# pm25.net
KiCad netlist of a schematic drawn in EAGLE
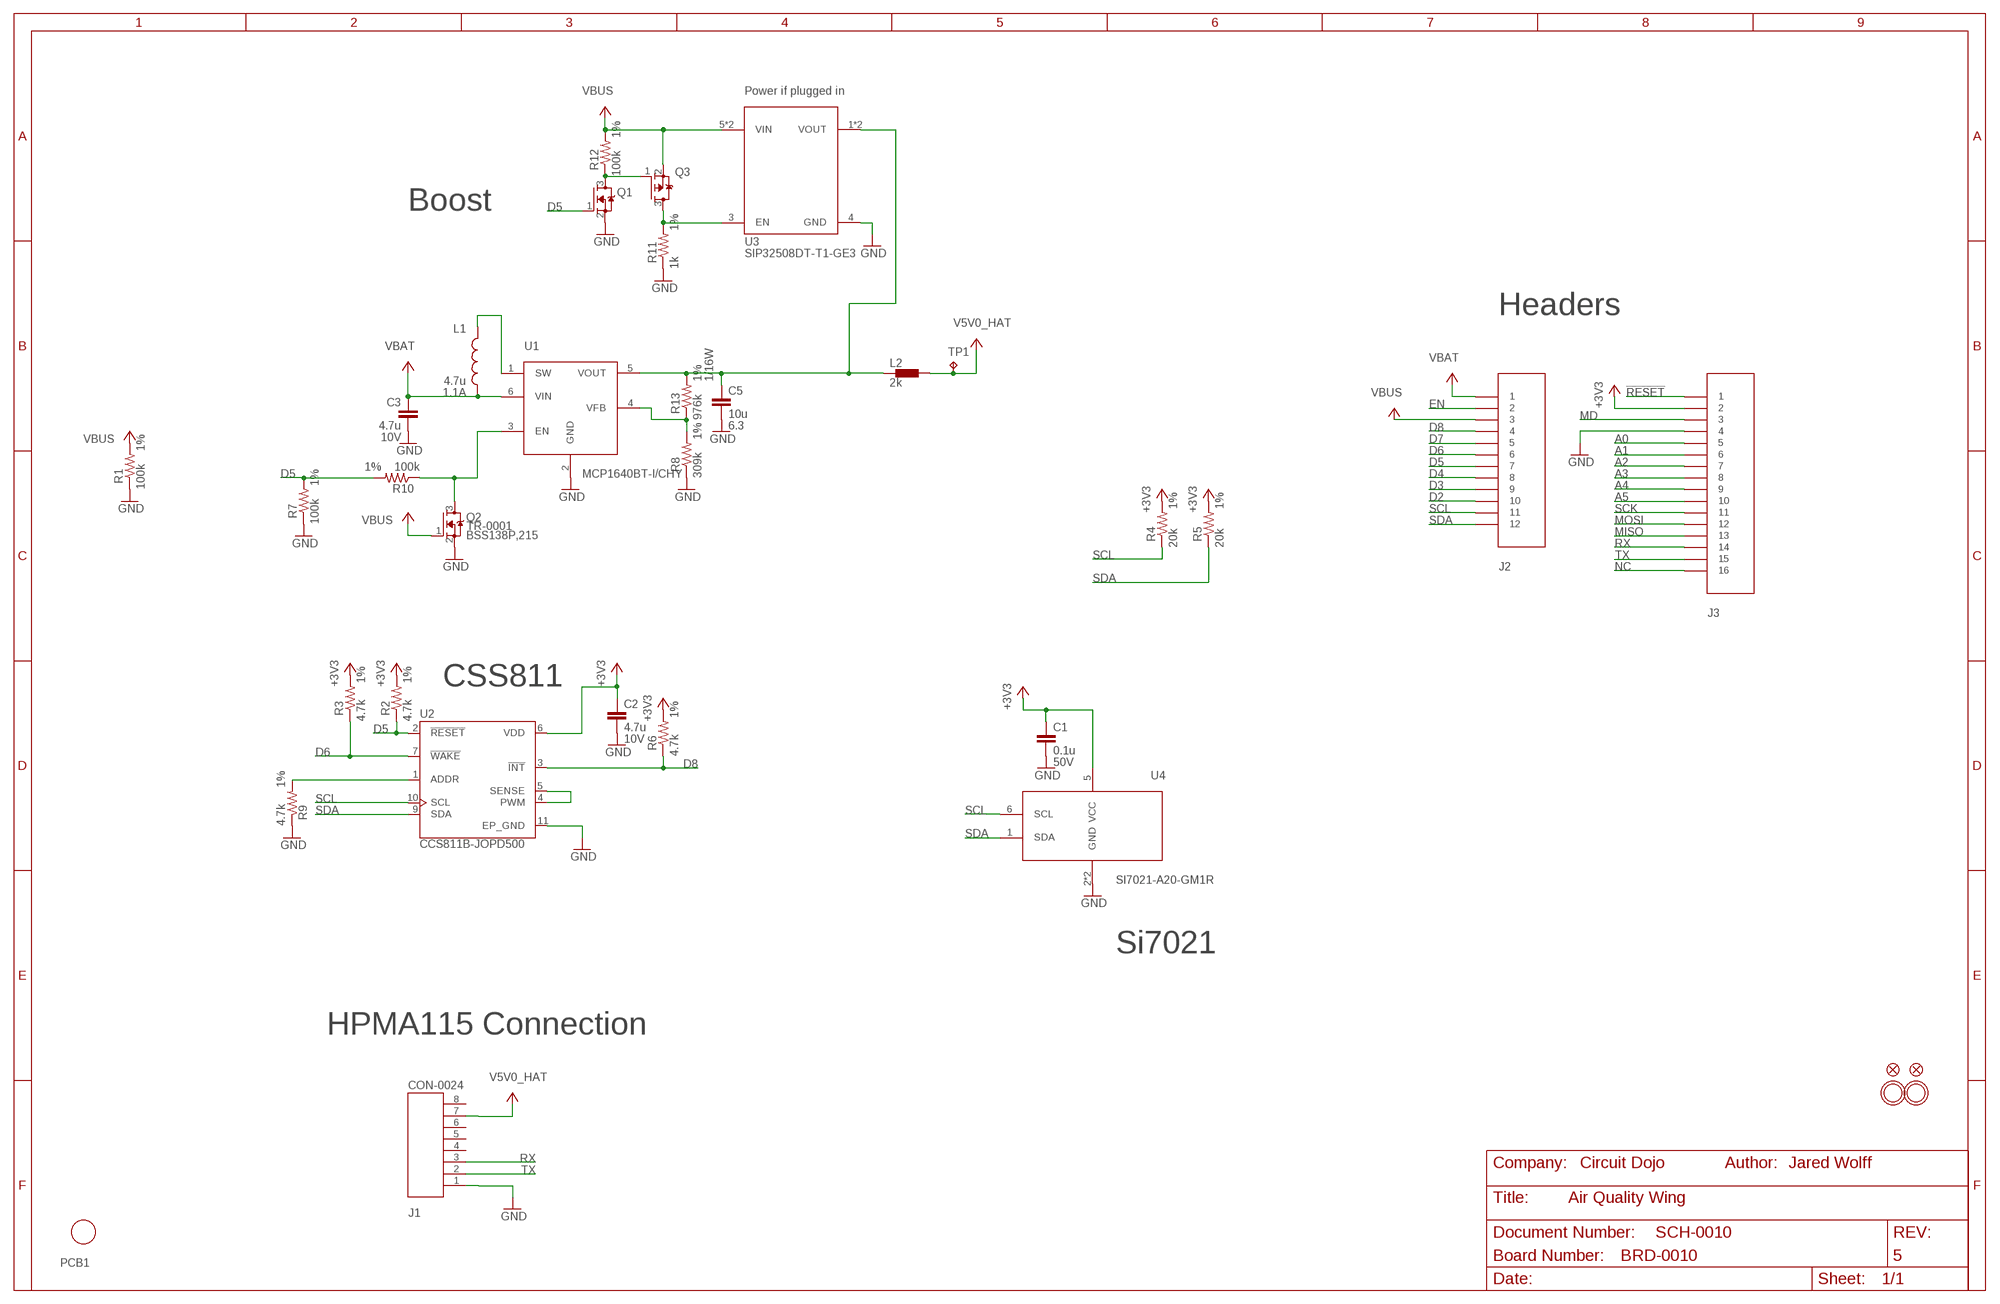
[diagram p0: schematic, sheet 1]

(export (version "E")
  (design (tool "Eeschema 10.0.6"))
  (components
    (comp (ref "C1")
      (value "0.1u")
      (footprint "eagle-import:CAPC1005X55N")
      (fields
        (field (name "VOLTHIGH") "50V")
        (field (name "MF") "Taiyo Yuden")
        (field (name "MPN") "UMK105BJ104KV-F")
      )
      (libsource (lib "eagle-import") (part "CAP-0017"))
    )
    (comp (ref "C2")
      (value "4.7u")
      (footprint "eagle-import:C0603")
      (fields (field (name "VOLTHIGH") "10V") (field (name "MPN") "CL10A475MP5LNNC"))
      (libsource (lib "eagle-import") (part "CAP-0010"))
    )
    (comp (ref "C3")
      (value "4.7u")
      (footprint "eagle-import:C0603")
      (fields (field (name "VOLTHIGH") "10V") (field (name "MPN") "CL10A475MP5LNNC"))
      (libsource (lib "eagle-import") (part "CAP-0010"))
    )
    (comp (ref "C5")
      (value "10u")
      (footprint "eagle-import:C0603")
      (fields (field (name "MPN") "JMK107ABJ106MA-T") (field (name "VOLTHIGH") "6.3"))
      (libsource (lib "eagle-import") (part "CAP-0603-10U-6.3V"))
    )
    (comp (ref "J1")
      (value "CON-0024")
      (footprint "eagle-import:0532610871")
      (fields (field (name "MPN") "0532610871"))
      (libsource (lib "eagle-import") (part "CON-0024"))
    )
    (comp (ref "J2")
      (value "HEADER-12")
      (footprint "eagle-import:CON-HEADER-1X12")
      (fields (field (name "MF") "Sullins Connector Solutions") (field (name "MPN") "PPPC121LFBN-RC"))
      (libsource (lib "eagle-import") (part "HEADER-12"))
    )
    (comp (ref "J3")
      (value "HEADER-16")
      (footprint "eagle-import:CON-HEADER-1X16")
      (fields (field (name "MF") "Sullins Connector Solutions") (field (name "MPN") "PPPC161LFBN-RC"))
      (libsource (lib "eagle-import") (part "HEADER-16"))
    )
    (comp (ref "L1")
      (value "4.7u")
      (footprint "eagle-import:IND-2P0X2P0X1P2")
      (fields (field (name "CURRENT") "1.1A") (field (name "MPN") "NRV2012T4R7MGF"))
      (libsource (lib "eagle-import") (part "IND-0003"))
    )
    (comp (ref "L2")
      (value "2k")
      (footprint "eagle-import:R0805")
      (fields (field (name "MPN") "CIM21J202NE"))
      (libsource (lib "eagle-import") (part "FERRITE-0805"))
    )
    (comp (ref "PCB1")
      (value "PCB-PS-CCS811-SI7021")
      (footprint "eagle-import:PLACEHOLDER")
      (fields (field (name "MPN") "BRD-0010"))
      (libsource (lib "eagle-import") (part "PCB-PS-CCS811-SI7021"))
    )
    (comp (ref "Q1")
      (value "TR-0001")
      (footprint "eagle-import:SOT23")
      (fields (field (name "MPN") "BSS138P,215"))
      (libsource (lib "eagle-import") (part "TR-0001"))
    )
    (comp (ref "Q2")
      (value "TR-0001")
      (footprint "eagle-import:SOT23")
      (fields (field (name "MPN") "BSS138P,215"))
      (libsource (lib "eagle-import") (part "TR-0001"))
    )
    (comp (ref "Q3")
      (value "TR-0003")
      (footprint "eagle-import:SOT23")
      (fields (field (name "MPN") "BSS84-7-F"))
      (libsource (lib "eagle-import") (part "TR-0003"))
    )
    (comp (ref "R1")
      (value "100k")
      (footprint "eagle-import:R0402")
      (fields
        (field (name "TOLERANCE") "1%")
        (field (name "POWER") "1/16W")
        (field (name "MPN") "RC0402FR07100KL")
      )
      (libsource (lib "eagle-import") (part "RES-0041"))
    )
    (comp (ref "R2")
      (value "4.7k")
      (footprint "eagle-import:R0402")
      (fields
        (field (name "MPN") "RC0402FR-074K7L")
        (field (name "POWER") "1/16W")
        (field (name "TOLERANCE") "1%")
      )
      (libsource (lib "eagle-import") (part "RES-0402-4.7K-1%"))
    )
    (comp (ref "R3")
      (value "4.7k")
      (footprint "eagle-import:R0402")
      (fields
        (field (name "MPN") "RC0402FR-074K7L")
        (field (name "POWER") "1/16W")
        (field (name "TOLERANCE") "1%")
      )
      (libsource (lib "eagle-import") (part "RES-0402-4.7K-1%"))
    )
    (comp (ref "R4")
      (value "20k")
      (footprint "eagle-import:R0402")
      (fields
        (field (name "TOLERANCE") "1%")
        (field (name "POWER") "1/16W")
        (field (name "MPN") "RC0402FR-0720KL")
      )
      (libsource (lib "eagle-import") (part "RES-0054"))
    )
    (comp (ref "R5")
      (value "20k")
      (footprint "eagle-import:R0402")
      (fields
        (field (name "TOLERANCE") "1%")
        (field (name "POWER") "1/16W")
        (field (name "MPN") "RC0402FR-0720KL")
      )
      (libsource (lib "eagle-import") (part "RES-0054"))
    )
    (comp (ref "R6")
      (value "4.7k")
      (footprint "eagle-import:R0402")
      (fields
        (field (name "MPN") "RC0402FR-074K7L")
        (field (name "POWER") "1/16W")
        (field (name "TOLERANCE") "1%")
      )
      (libsource (lib "eagle-import") (part "RES-0402-4.7K-1%"))
    )
    (comp (ref "R7")
      (value "100k")
      (footprint "eagle-import:R0402")
      (fields
        (field (name "TOLERANCE") "1%")
        (field (name "POWER") "1/16W")
        (field (name "MPN") "RC0402FR07100KL")
      )
      (libsource (lib "eagle-import") (part "RES-0041"))
    )
    (comp (ref "R8")
      (value "309k")
      (footprint "eagle-import:R0402")
      (fields
        (field (name "MPN") "RC0402FR-07309KL")
        (field (name "POWER") "1/16W")
        (field (name "TOLERANCE") "1%")
      )
      (libsource (lib "eagle-import") (part "RES-0402-309K-1%"))
    )
    (comp (ref "R9")
      (value "4.7k")
      (footprint "eagle-import:R0402")
      (fields
        (field (name "MPN") "RC0402FR-074K7L")
        (field (name "POWER") "1/16W")
        (field (name "TOLERANCE") "1%")
      )
      (libsource (lib "eagle-import") (part "RES-0402-4.7K-1%"))
    )
    (comp (ref "R10")
      (value "100k")
      (footprint "eagle-import:R0402")
      (fields
        (field (name "TOLERANCE") "1%")
        (field (name "POWER") "1/16W")
        (field (name "MPN") "RC0402FR07100KL")
      )
      (libsource (lib "eagle-import") (part "RES-0041"))
    )
    (comp (ref "R11")
      (value "1k")
      (footprint "eagle-import:R0402")
      (fields
        (field (name "MPN") "RCS04021K00FKED")
        (field (name "POWER") "1/5W")
        (field (name "TOLERANCE") "1%")
      )
      (libsource (lib "eagle-import") (part "RES-0402-1K-1%"))
    )
    (comp (ref "R12")
      (value "100k")
      (footprint "eagle-import:R0402")
      (fields
        (field (name "TOLERANCE") "1%")
        (field (name "POWER") "1/16W")
        (field (name "MPN") "RC0402FR07100KL")
      )
      (libsource (lib "eagle-import") (part "RES-0041"))
    )
    (comp (ref "R13")
      (value "976k")
      (footprint "eagle-import:R0402")
      (fields
        (field (name "MPN") "RC0402FR-07976KL")
        (field (name "POWER") "1/16W")
        (field (name "TOLERANCE") "1%")
      )
      (libsource (lib "eagle-import") (part "RES-0402-976K-1%"))
    )
    (comp (ref "TP1")
      (value "TP")
      (footprint "eagle-import:TP-1P27")
      (libsource (lib "eagle-import") (part "TP"))
    )
    (comp (ref "U$31")
      (value "MOUNTINGHOLE2.5")
      (footprint "eagle-import:MOUNTINGHOLE_2.5_PLATED")
      (libsource (lib "eagle-import") (part "MOUNTINGHOLE2.5"))
    )
    (comp (ref "U$32")
      (value "MOUNTINGHOLE2.5")
      (footprint "eagle-import:MOUNTINGHOLE_2.5_PLATED")
      (libsource (lib "eagle-import") (part "MOUNTINGHOLE2.5"))
    )
    (comp (ref "U$34")
      (value "FIDUCIAL\"\"")
      (footprint "eagle-import:FIDUCIAL_1MM")
      (libsource (lib "eagle-import") (part "FIDUCIAL{dblquote}{dblquote}"))
    )
    (comp (ref "U$35")
      (value "FIDUCIAL\"\"")
      (footprint "eagle-import:FIDUCIAL_1MM")
      (libsource (lib "eagle-import") (part "FIDUCIAL{dblquote}{dblquote}"))
    )
    (comp (ref "U1")
      (value "POWER-VREG-FB-EN-SW-350MA")
      (footprint "eagle-import:SOT23-6")
      (fields (field (name "MPN") "MCP1640BT-I/CHY"))
      (libsource (lib "eagle-import") (part "POWER-VREG-FB-EN-SW-350MA"))
    )
    (comp (ref "U2")
      (value "CCS811B-JOPD500")
      (footprint "eagle-import:SON60P400X270X110-11N")
      (fields (field (name "MF") "ams"))
      (libsource (lib "eagle-import") (part "CCS811B-JOPD500"))
    )
    (comp (ref "U3")
      (value "POWER-SWITCH-SIP32508-SO23-6")
      (footprint "eagle-import:SOT23-6")
      (fields (field (name "MPN") "SIP32508DT-T1-GE3"))
      (libsource (lib "eagle-import") (part "POWER-SWITCH-SO23-6-SIP32508"))
    )
    (comp (ref "U4")
      (value "SI7021-A20-GM1R")
      (footprint "eagle-import:SON100P300X300X80-7N")
      (fields (field (name "MPN") "SI7021-A20-GM1R"))
      (libsource (lib "eagle-import") (part "SI7021-A20-GM1R"))
    )
  )
  (nets
    (net (code "1") (name "+3V3") (class "Default")
      (node (ref "C1") (pin "1") (pinfunction "1_1") (pintype "passive"))
      (node (ref "C2") (pin "1") (pinfunction "1_1") (pintype "passive"))
      (node (ref "J3") (pin "2") (pinfunction "2_2") (pintype "bidirectional"))
      (node (ref "R2") (pin "2") (pinfunction "2_2") (pintype "passive"))
      (node (ref "R3") (pin "2") (pinfunction "2_2") (pintype "passive"))
      (node (ref "R4") (pin "2") (pinfunction "2_2") (pintype "passive"))
      (node (ref "R5") (pin "2") (pinfunction "2_2") (pintype "passive"))
      (node (ref "R6") (pin "2") (pinfunction "2_2") (pintype "passive"))
      (node (ref "U2") (pin "6") (pinfunction "VDD_6") (pintype "power_in"))
      (node (ref "U4") (pin "5") (pinfunction "VCC_5") (pintype "bidirectional"))
    )
    (net (code "2") (name "/A0") (class "Default")
      (node (ref "J3") (pin "5") (pinfunction "5_5") (pintype "bidirectional"))
    )
    (net (code "3") (name "/A1") (class "Default")
      (node (ref "J3") (pin "6") (pinfunction "6_6") (pintype "bidirectional"))
    )
    (net (code "4") (name "/A2") (class "Default")
      (node (ref "J3") (pin "7") (pinfunction "7_7") (pintype "bidirectional"))
    )
    (net (code "5") (name "/A3") (class "Default")
      (node (ref "J3") (pin "8") (pinfunction "8_8") (pintype "bidirectional"))
    )
    (net (code "6") (name "/A4") (class "Default")
      (node (ref "J3") (pin "9") (pinfunction "9_9") (pintype "bidirectional"))
    )
    (net (code "7") (name "/A5") (class "Default")
      (node (ref "J3") (pin "10") (pinfunction "10_10") (pintype "bidirectional"))
    )
    (net (code "8") (name "/D2") (class "Default")
      (node (ref "J2") (pin "10") (pinfunction "10_10") (pintype "bidirectional"))
    )
    (net (code "9") (name "/D3") (class "Default")
      (node (ref "J2") (pin "9") (pinfunction "9_9") (pintype "bidirectional"))
    )
    (net (code "10") (name "/D4") (class "Default")
      (node (ref "J2") (pin "8") (pinfunction "8_8") (pintype "bidirectional"))
    )
    (net (code "11") (name "/D5") (class "Default")
      (node (ref "J2") (pin "7") (pinfunction "7_7") (pintype "bidirectional"))
      (node (ref "Q1") (pin "1") (pinfunction "G_1") (pintype "bidirectional"))
      (node (ref "R10") (pin "2") (pinfunction "2_2") (pintype "passive"))
      (node (ref "R2") (pin "1") (pinfunction "1_1") (pintype "passive"))
      (node (ref "R7") (pin "2") (pinfunction "2_2") (pintype "passive"))
      (node (ref "U2") (pin "2") (pinfunction "~{RESET}_2") (pintype "input"))
    )
    (net (code "12") (name "/D6") (class "Default")
      (node (ref "J2") (pin "6") (pinfunction "6_6") (pintype "bidirectional"))
      (node (ref "R3") (pin "1") (pinfunction "1_1") (pintype "passive"))
      (node (ref "U2") (pin "7") (pinfunction "~{WAKE}_7") (pintype "input"))
    )
    (net (code "13") (name "/D7") (class "Default")
      (node (ref "J2") (pin "5") (pinfunction "5_5") (pintype "bidirectional"))
    )
    (net (code "14") (name "/D8") (class "Default")
      (node (ref "J2") (pin "4") (pinfunction "4_4") (pintype "bidirectional"))
      (node (ref "R6") (pin "1") (pinfunction "1_1") (pintype "passive"))
      (node (ref "U2") (pin "3") (pinfunction "~{INT}_3") (pintype "output"))
    )
    (net (code "15") (name "/EN") (class "Default")
      (node (ref "J2") (pin "2") (pinfunction "2_2") (pintype "bidirectional"))
    )
    (net (code "16") (name "/MD") (class "Default")
      (node (ref "J3") (pin "3") (pinfunction "3_3") (pintype "bidirectional"))
    )
    (net (code "17") (name "/MISO") (class "Default")
      (node (ref "J3") (pin "13") (pinfunction "13_13") (pintype "bidirectional"))
    )
    (net (code "18") (name "/MOSI") (class "Default")
      (node (ref "J3") (pin "12") (pinfunction "12_12") (pintype "bidirectional"))
    )
    (net (code "19") (name "/NC") (class "Default")
      (node (ref "J3") (pin "16") (pinfunction "16_16") (pintype "bidirectional"))
    )
    (net (code "20") (name "/RX") (class "Default")
      (node (ref "J1") (pin "3") (pinfunction "P$3_3") (pintype "bidirectional"))
      (node (ref "J3") (pin "14") (pinfunction "14_14") (pintype "bidirectional"))
    )
    (net (code "21") (name "/SCK") (class "Default")
      (node (ref "J3") (pin "11") (pinfunction "11_11") (pintype "bidirectional"))
    )
    (net (code "22") (name "/SCL") (class "Default")
      (node (ref "J2") (pin "11") (pinfunction "11_11") (pintype "bidirectional"))
      (node (ref "R4") (pin "1") (pinfunction "1_1") (pintype "passive"))
      (node (ref "U2") (pin "10") (pinfunction "SCL_10") (pintype "input"))
      (node (ref "U4") (pin "6") (pinfunction "SCL_6") (pintype "bidirectional"))
    )
    (net (code "23") (name "/SDA") (class "Default")
      (node (ref "J2") (pin "12") (pinfunction "12_12") (pintype "bidirectional"))
      (node (ref "R5") (pin "1") (pinfunction "1_1") (pintype "passive"))
      (node (ref "U2") (pin "9") (pinfunction "SDA_9") (pintype "bidirectional"))
      (node (ref "U4") (pin "1") (pinfunction "SDA_1") (pintype "bidirectional"))
    )
    (net (code "24") (name "/TX") (class "Default")
      (node (ref "J1") (pin "2") (pinfunction "P$2_2") (pintype "bidirectional"))
      (node (ref "J3") (pin "15") (pinfunction "15_15") (pintype "bidirectional"))
    )
    (net (code "25") (name "/~{RESET}") (class "Default")
      (node (ref "J3") (pin "1") (pinfunction "1_1") (pintype "bidirectional"))
    )
    (net (code "26") (name "GND") (class "Default")
      (node (ref "C1") (pin "2") (pinfunction "2_2") (pintype "passive"))
      (node (ref "C2") (pin "2") (pinfunction "2_2") (pintype "passive"))
      (node (ref "C3") (pin "2") (pinfunction "2_2") (pintype "passive"))
      (node (ref "C5") (pin "2") (pinfunction "2_2") (pintype "passive"))
      (node (ref "J1") (pin "1") (pinfunction "P$1_1") (pintype "bidirectional"))
      (node (ref "J3") (pin "4") (pinfunction "4_4") (pintype "bidirectional"))
      (node (ref "Q1") (pin "2") (pinfunction "S_2") (pintype "bidirectional"))
      (node (ref "Q2") (pin "2") (pinfunction "S_2") (pintype "bidirectional"))
      (node (ref "R1") (pin "1") (pinfunction "1_1") (pintype "passive"))
      (node (ref "R11") (pin "1") (pinfunction "1_1") (pintype "passive"))
      (node (ref "R7") (pin "1") (pinfunction "1_1") (pintype "passive"))
      (node (ref "R8") (pin "1") (pinfunction "1_1") (pintype "passive"))
      (node (ref "R9") (pin "1") (pinfunction "1_1") (pintype "passive"))
      (node (ref "U1") (pin "2") (pinfunction "GND_2") (pintype "bidirectional"))
      (node (ref "U2") (pin "11") (pinfunction "EP_GND_11") (pintype "power_in"))
      (node (ref "U3") (pin "4") (pinfunction "GND_4") (pintype "power_in"))
      (node (ref "U4") (pin "2") (pinfunction "GND_2") (pintype "bidirectional"))
      (node (ref "U4") (pin "7") (pinfunction "GND_7") (pintype "bidirectional"))
    )
    (net (code "27") (name "Net-(L1-1)") (class "Default")
      (node (ref "L1") (pin "P$1") (pinfunction "1_P$1") (pintype "passive"))
      (node (ref "U1") (pin "1") (pinfunction "SW_1") (pintype "bidirectional"))
    )
    (net (code "28") (name "Net-(Q1-D)") (class "Default")
      (node (ref "Q1") (pin "3") (pinfunction "D_3") (pintype "bidirectional"))
      (node (ref "Q3") (pin "1") (pinfunction "G_1") (pintype "passive"))
      (node (ref "R12") (pin "1") (pinfunction "1_1") (pintype "passive"))
    )
    (net (code "29") (name "Net-(Q2-D)") (class "Default")
      (node (ref "Q2") (pin "3") (pinfunction "D_3") (pintype "bidirectional"))
      (node (ref "R10") (pin "1") (pinfunction "1_1") (pintype "passive"))
      (node (ref "U1") (pin "3") (pinfunction "EN_3") (pintype "bidirectional"))
    )
    (net (code "30") (name "Net-(Q3-D)") (class "Default")
      (node (ref "Q3") (pin "3") (pinfunction "D_3") (pintype "passive"))
      (node (ref "R11") (pin "2") (pinfunction "2_2") (pintype "passive"))
      (node (ref "U3") (pin "3") (pinfunction "EN_3") (pintype "input"))
    )
    (net (code "31") (name "Net-(U1-VFB)") (class "Default")
      (node (ref "R13") (pin "1") (pinfunction "1_1") (pintype "passive"))
      (node (ref "R8") (pin "2") (pinfunction "2_2") (pintype "passive"))
      (node (ref "U1") (pin "4") (pinfunction "VFB_4") (pintype "bidirectional"))
    )
    (net (code "32") (name "Net-(U1-VOUT)") (class "Default")
      (node (ref "C5") (pin "1") (pinfunction "1_1") (pintype "passive"))
      (node (ref "L2") (pin "1") (pinfunction "1_1") (pintype "passive"))
      (node (ref "R13") (pin "2") (pinfunction "2_2") (pintype "passive"))
      (node (ref "U1") (pin "5") (pinfunction "VOUT_5") (pintype "bidirectional"))
      (node (ref "U3") (pin "1") (pinfunction "VOUT_1") (pintype "power_in"))
      (node (ref "U3") (pin "2") (pinfunction "VOUT_2") (pintype "power_in"))
    )
    (net (code "33") (name "Net-(U2-ADDR)") (class "Default")
      (node (ref "R9") (pin "2") (pinfunction "2_2") (pintype "passive"))
      (node (ref "U2") (pin "1") (pinfunction "ADDR_1") (pintype "input"))
    )
    (net (code "34") (name "Net-(U2-PWM)") (class "Default")
      (node (ref "U2") (pin "4") (pinfunction "PWM_4") (pintype "output"))
      (node (ref "U2") (pin "5") (pinfunction "SENSE_5") (pintype "output"))
    )
    (net (code "35") (name "V5V0_HAT") (class "Default")
      (node (ref "J1") (pin "7") (pinfunction "P$7_7") (pintype "bidirectional"))
      (node (ref "L2") (pin "2") (pinfunction "2_2") (pintype "passive"))
      (node (ref "TP1") (pin "P$1") (pinfunction "TP_P$1") (pintype "input"))
      (node (ref "TP1") (pin "P$2") (pinfunction "TP_P$2") (pintype "input"))
      (node (ref "TP1") (pin "TP") (pinfunction "TP_TP") (pintype "input"))
    )
    (net (code "36") (name "VBAT") (class "Default")
      (node (ref "C3") (pin "1") (pinfunction "1_1") (pintype "passive"))
      (node (ref "J2") (pin "1") (pinfunction "1_1") (pintype "bidirectional"))
      (node (ref "L1") (pin "P$2") (pinfunction "2_P$2") (pintype "passive"))
      (node (ref "U1") (pin "6") (pinfunction "VIN_6") (pintype "bidirectional"))
    )
    (net (code "37") (name "VBUS") (class "Default")
      (node (ref "J2") (pin "3") (pinfunction "3_3") (pintype "bidirectional"))
      (node (ref "Q2") (pin "1") (pinfunction "G_1") (pintype "bidirectional"))
      (node (ref "Q3") (pin "2") (pinfunction "S_2") (pintype "passive"))
      (node (ref "R1") (pin "2") (pinfunction "2_2") (pintype "passive"))
      (node (ref "R12") (pin "2") (pinfunction "2_2") (pintype "passive"))
      (node (ref "U3") (pin "5") (pinfunction "VIN_5") (pintype "power_in"))
      (node (ref "U3") (pin "6") (pinfunction "VIN_6") (pintype "power_in"))
    )
    (net (code "38") (name "unconnected-(J1-P$4-Pad4)") (class "Default")
      (node (ref "J1") (pin "4") (pinfunction "P$4_4") (pintype "bidirectional"))
    )
    (net (code "39") (name "unconnected-(J1-P$5-Pad5)") (class "Default")
      (node (ref "J1") (pin "5") (pinfunction "P$5_5") (pintype "bidirectional"))
    )
    (net (code "40") (name "unconnected-(J1-P$6-Pad6)") (class "Default")
      (node (ref "J1") (pin "6") (pinfunction "P$6_6") (pintype "bidirectional"))
    )
    (net (code "41") (name "unconnected-(J1-P$8-Pad8)") (class "Default")
      (node (ref "J1") (pin "8") (pinfunction "P$8_8") (pintype "bidirectional"))
    )
  )
)
